# SCH_d_01_ex_00.net
KiCad netlist of a schematic drawn in EasyEDA
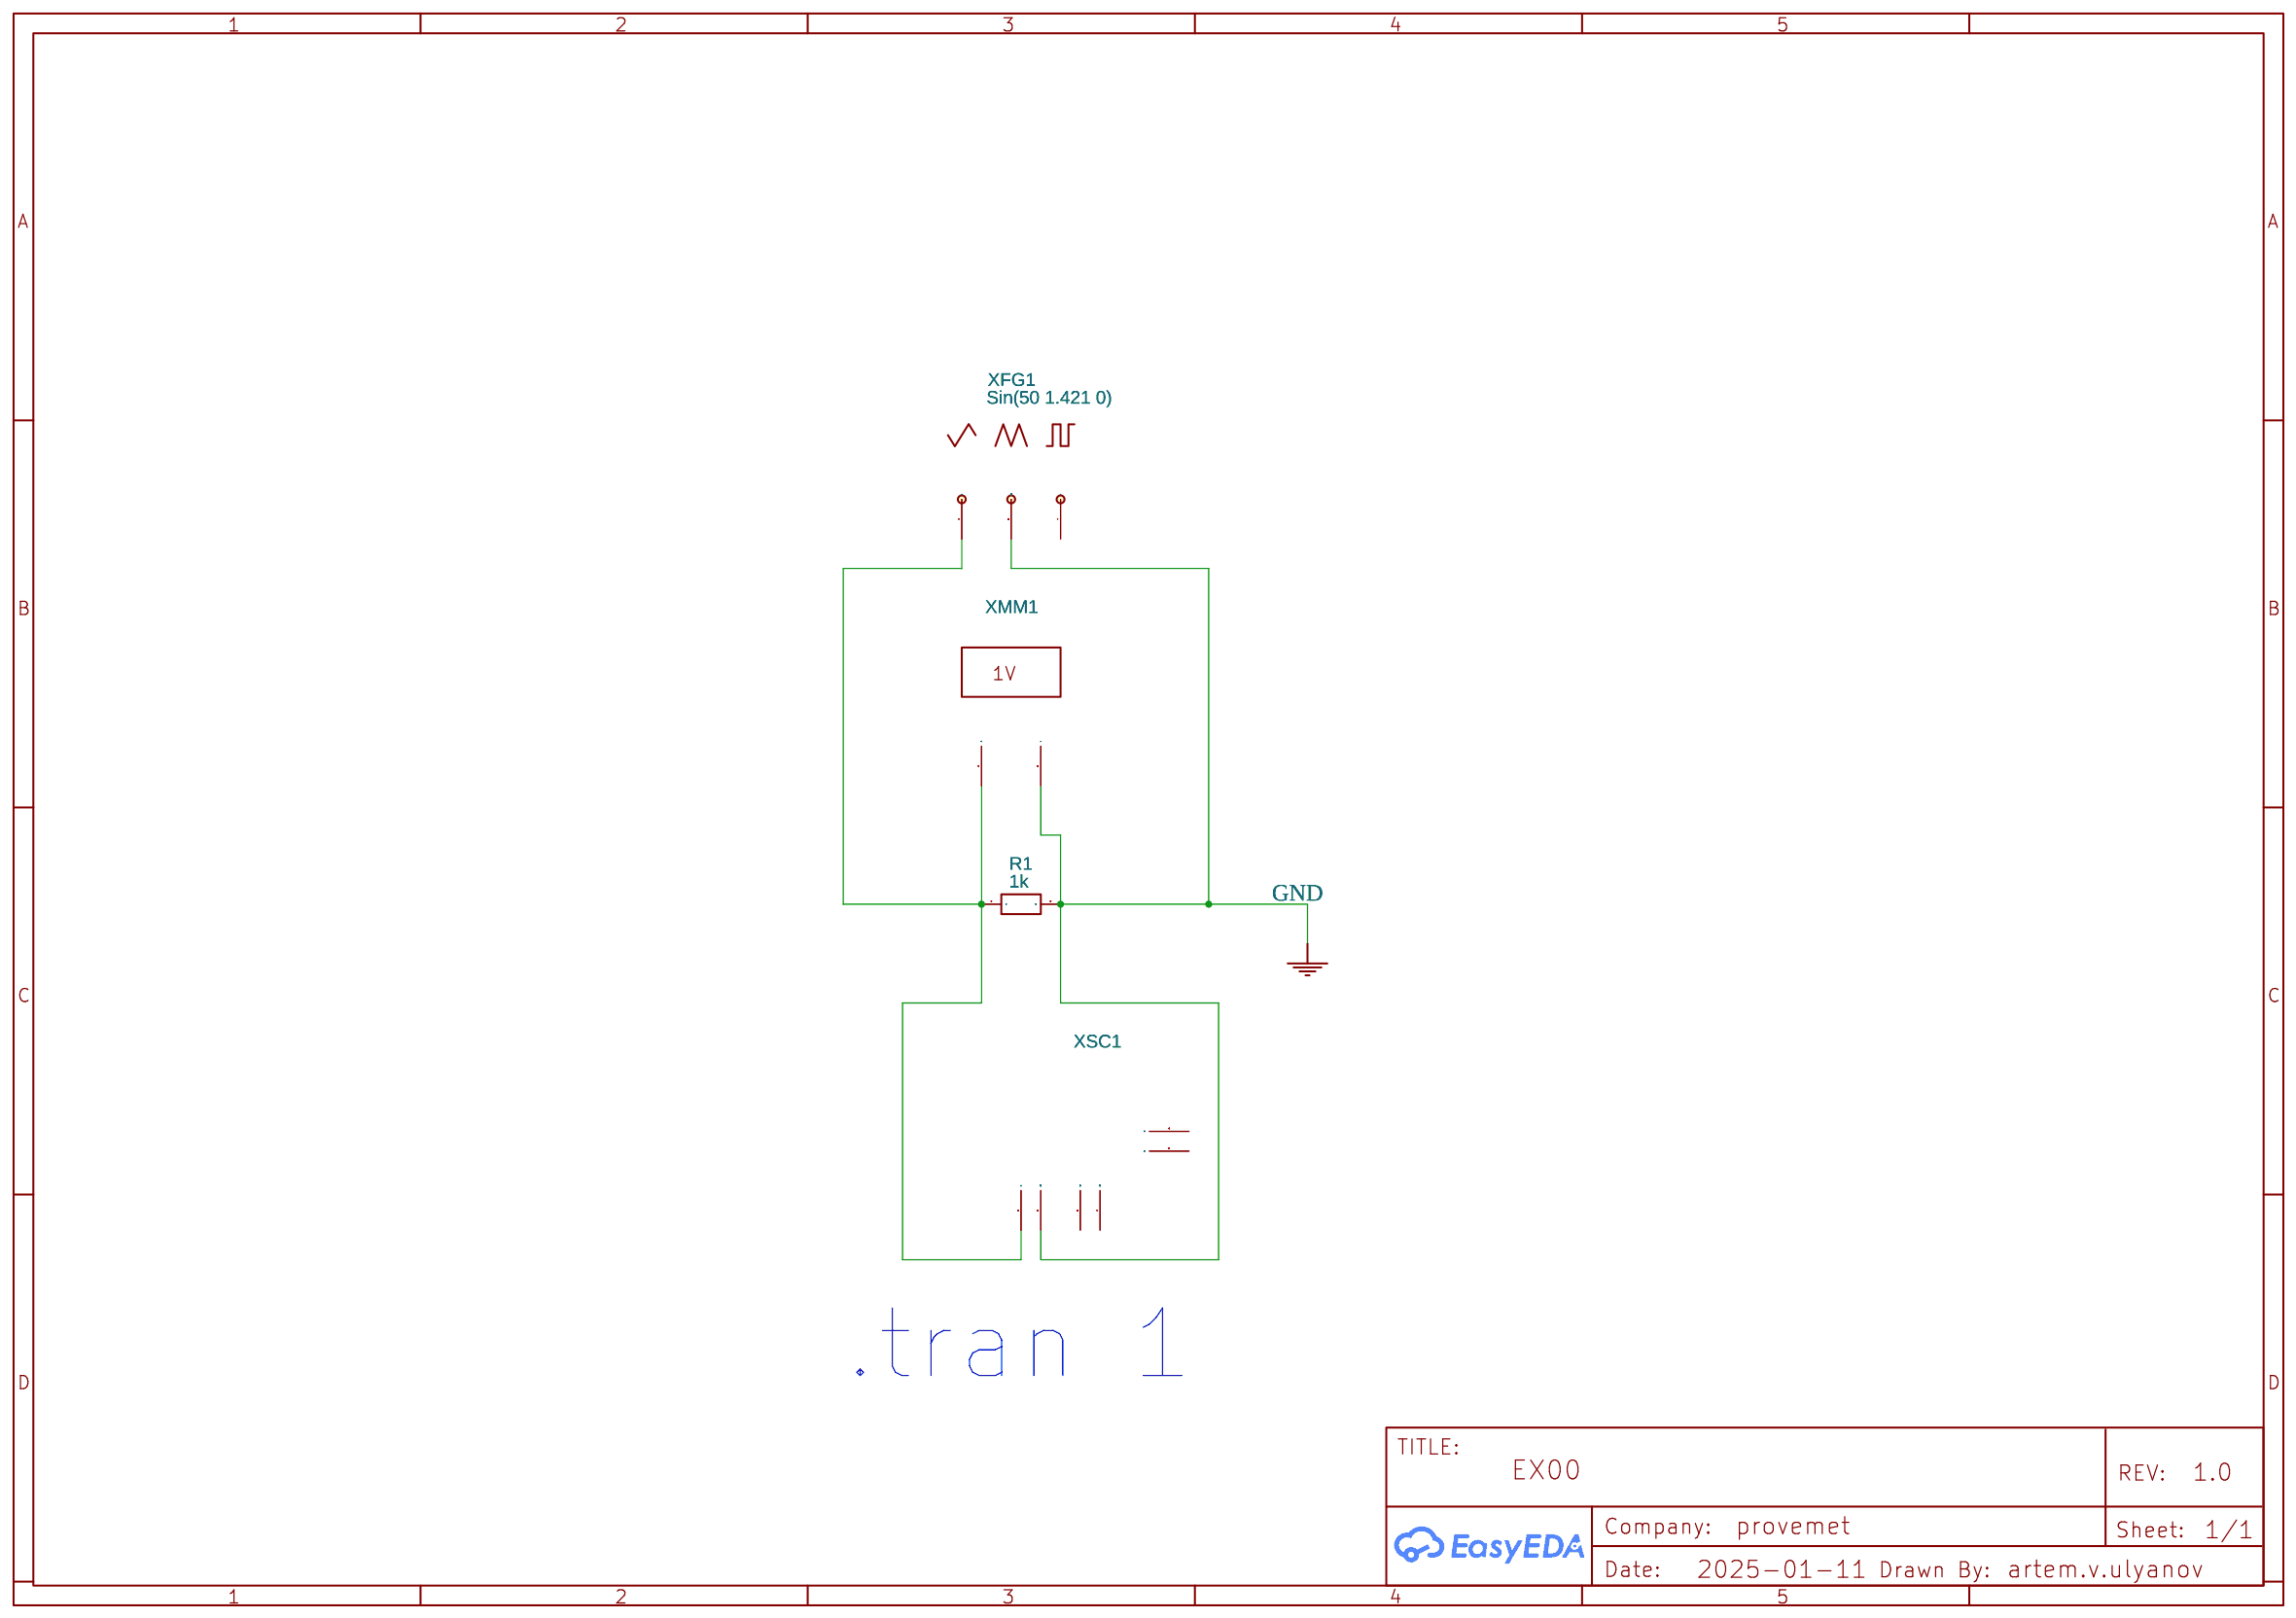
[diagram p0: schematic sheet]

(export (version "E")
  (design (tool "Eeschema 10.0.6"))
  (components
    (comp (ref "R1") (value "1k") (libsource (lib "") (part "R_0603_EU")))
    (comp (ref "XFG1") (value "Sin(50 1.421 0)") (libsource (lib "") (part "FUNCTIONGENERATOR")))
    (comp (ref "XMM1") (value "Multimeter") (libsource (lib "") (part "MULTIMETER")))
    (comp (ref "XSC1") (value "Oscilloscope") (libsource (lib "") (part "OSCILLOSCOPE")))
  )
  (nets
    (net (code "1") (name "GND") (class "Default")
      (node (ref "R1") (pin "2") (pinfunction "2_2") (pintype "unspecified"))
      (node (ref "XFG1") (pin "COM") (pinfunction "COM_COM") (pintype "unspecified"))
      (node (ref "XMM1") (pin "2") (pinfunction "I_2") (pintype "unspecified"))
      (node (ref "XSC1") (pin "2") (pinfunction "GND1_2") (pintype "unspecified"))
    )
    (net (code "2") (name "Net-(XMM1-+)") (class "Default")
      (node (ref "R1") (pin "1") (pinfunction "1_1") (pintype "unspecified"))
      (node (ref "XFG1") (pin "+") (pinfunction "+_+") (pintype "unspecified"))
      (node (ref "XMM1") (pin "1") (pinfunction "+_1") (pintype "unspecified"))
      (node (ref "XSC1") (pin "1") (pinfunction "A_1") (pintype "unspecified"))
    )
    (net (code "3") (name "unconnected-(XFG1-Pad-)") (class "Default")
      (node (ref "XFG1") (pin "-") (pinfunction "-_-") (pintype "unspecified"))
    )
    (net (code "4") (name "unconnected-(XSC1-B-Pad3)") (class "Default")
      (node (ref "XSC1") (pin "3") (pinfunction "B_3") (pintype "unspecified"))
    )
    (net (code "5") (name "unconnected-(XSC1-GND2-Pad4)") (class "Default")
      (node (ref "XSC1") (pin "4") (pinfunction "GND2_4") (pintype "unspecified"))
    )
    (net (code "6") (name "unconnected-(XSC1-T+-Pad5)") (class "Default")
      (node (ref "XSC1") (pin "5") (pinfunction "T+_5") (pintype "unspecified"))
    )
    (net (code "7") (name "unconnected-(XSC1-T--Pad6)") (class "Default")
      (node (ref "XSC1") (pin "6") (pinfunction "T-_6") (pintype "unspecified"))
    )
  )
)
